# GD32F207RG.net
KiCad netlist of a schematic drawn in EAGLE
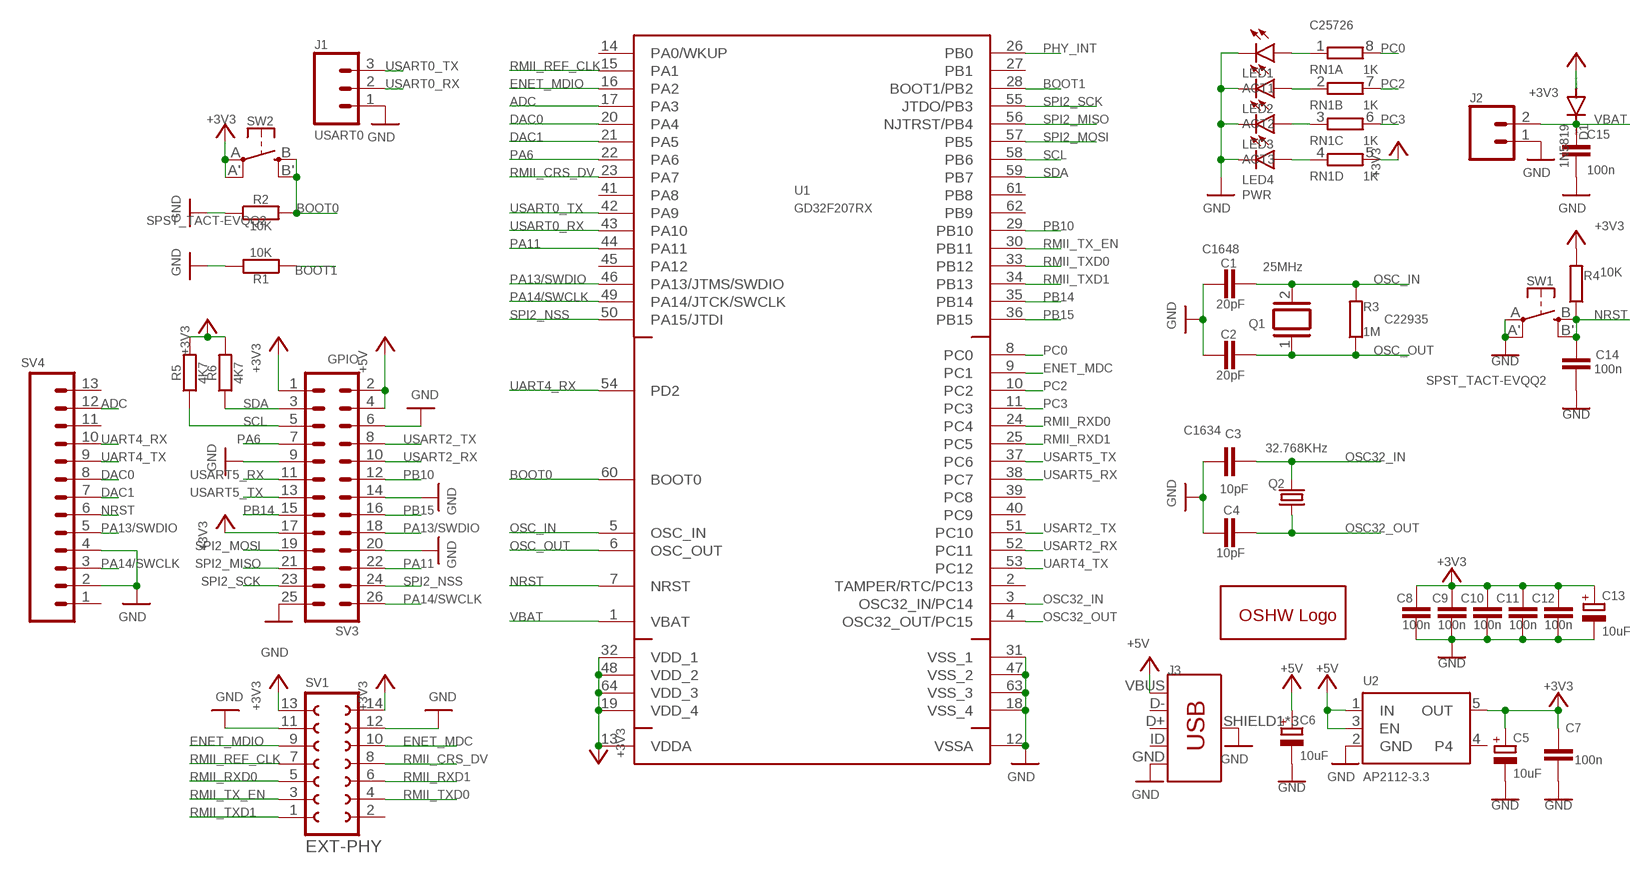
[diagram p0: schematic, sheet 1]

(export (version "E")
  (design (tool "Eeschema 10.0.6"))
  (components
    (comp (ref "C1")
      (value "20pF")
      (footprint "eagle-import:C0603")
      (fields (field (name "JLCPCB") "C1648"))
      (libsource (lib "eagle-import") (part "C-EUC0603"))
    )
    (comp (ref "C2")
      (value "20pF")
      (footprint "eagle-import:C0603")
      (libsource (lib "eagle-import") (part "C-EUC0603"))
    )
    (comp (ref "C3")
      (value "10pF")
      (footprint "eagle-import:C0603")
      (fields (field (name "JLCPCB") "C1634"))
      (libsource (lib "eagle-import") (part "C-EUC0603"))
    )
    (comp (ref "C4")
      (value "10pF")
      (footprint "eagle-import:C0603")
      (libsource (lib "eagle-import") (part "C-EUC0603"))
    )
    (comp (ref "C5")
      (value "10uF")
      (footprint "eagle-import:A_3216-18R")
      (libsource (lib "eagle-import") (part "CPOL-EUA/3216-18R"))
    )
    (comp (ref "C6")
      (value "10uF")
      (footprint "eagle-import:A_3216-18R")
      (libsource (lib "eagle-import") (part "CPOL-EUA/3216-18R"))
    )
    (comp (ref "C7")
      (value "100n")
      (footprint "eagle-import:C0603")
      (libsource (lib "eagle-import") (part "C-EUC0603"))
    )
    (comp (ref "C8")
      (value "100n")
      (footprint "eagle-import:C0603")
      (libsource (lib "eagle-import") (part "C-EUC0603"))
    )
    (comp (ref "C9")
      (value "100n")
      (footprint "eagle-import:C0603")
      (libsource (lib "eagle-import") (part "C-EUC0603"))
    )
    (comp (ref "C10")
      (value "100n")
      (footprint "eagle-import:C0603")
      (libsource (lib "eagle-import") (part "C-EUC0603"))
    )
    (comp (ref "C11")
      (value "100n")
      (footprint "eagle-import:C0603")
      (libsource (lib "eagle-import") (part "C-EUC0603"))
    )
    (comp (ref "C12")
      (value "100n")
      (footprint "eagle-import:C0603")
      (libsource (lib "eagle-import") (part "C-EUC0603"))
    )
    (comp (ref "C13")
      (value "10uF")
      (footprint "eagle-import:A_3216-18R")
      (libsource (lib "eagle-import") (part "CPOL-EUA/3216-18R"))
    )
    (comp (ref "C14")
      (value "100n")
      (footprint "eagle-import:C0603")
      (libsource (lib "eagle-import") (part "C-EUC0603"))
    )
    (comp (ref "C15")
      (value "100n")
      (footprint "eagle-import:C0603")
      (libsource (lib "eagle-import") (part "C-EUC0603"))
    )
    (comp (ref "D1")
      (value "1N5819")
      (footprint "eagle-import:SOD323-R")
      (libsource (lib "eagle-import") (part "DIODE-SOD323-R"))
    )
    (comp (ref "GOLD_ORB_SM1")
      (value "OSHWLOGOLOGO5MM")
      (footprint "eagle-import:OSHW_5MM")
      (libsource (lib "eagle-import") (part "OSHWLOGOLOGO5MM"))
    )
    (comp (ref "J1")
      (value "USART0")
      (footprint "eagle-import:1X03")
      (libsource (lib "eagle-import") (part "CONN_03"))
    )
    (comp (ref "J2")
      (value "CONN_02JST-PTH-2")
      (footprint "eagle-import:JST-2-PTH")
      (libsource (lib "eagle-import") (part "CONN_02JST-PTH-2"))
    )
    (comp (ref "J3")
      (value "USB_MICRO-B_FEMALE-SMT")
      (footprint "eagle-import:USB-B-MICRO-SMD")
      (libsource (lib "eagle-import") (part "USB_MICRO-B_FEMALE-SMT"))
    )
    (comp (ref "LED1")
      (value "ACT1")
      (footprint "eagle-import:CHIP-LED0603")
      (libsource (lib "eagle-import") (part "LEDCHIP-LED0603"))
    )
    (comp (ref "LED2")
      (value "ACT2")
      (footprint "eagle-import:CHIP-LED0603")
      (libsource (lib "eagle-import") (part "LEDCHIP-LED0603"))
    )
    (comp (ref "LED3")
      (value "ACT3")
      (footprint "eagle-import:CHIP-LED0603")
      (libsource (lib "eagle-import") (part "LEDCHIP-LED0603"))
    )
    (comp (ref "LED4")
      (value "PWR")
      (footprint "eagle-import:CHIP-LED0603")
      (libsource (lib "eagle-import") (part "LEDCHIP-LED0603"))
    )
    (comp (ref "Q1")
      (value "25MHz")
      (footprint "eagle-import:QS")
      (libsource (lib "eagle-import") (part "XTAL/S"))
    )
    (comp (ref "Q2")
      (value "32.768KHz")
      (footprint "eagle-import:TC26H")
      (libsource (lib "eagle-import") (part "CRYSTALTC26H"))
    )
    (comp (ref "R1")
      (value "10K")
      (footprint "eagle-import:R0603")
      (libsource (lib "eagle-import") (part "R-EU_R0603"))
    )
    (comp (ref "R2")
      (value "10K")
      (footprint "eagle-import:R0603")
      (libsource (lib "eagle-import") (part "R-EU_R0603"))
    )
    (comp (ref "R3")
      (value "1M")
      (footprint "eagle-import:R0603")
      (fields (field (name "JLCPCB") "C22935"))
      (libsource (lib "eagle-import") (part "R-EU_R0603"))
    )
    (comp (ref "R4")
      (value "10K")
      (footprint "eagle-import:R0603")
      (libsource (lib "eagle-import") (part "R-EU_R0603"))
    )
    (comp (ref "R5")
      (value "4K7")
      (footprint "eagle-import:R0603")
      (libsource (lib "eagle-import") (part "R-EU_R0603"))
    )
    (comp (ref "R6")
      (value "4K7")
      (footprint "eagle-import:R0603")
      (libsource (lib "eagle-import") (part "R-EU_R0603"))
    )
    (comp (ref "RN1")
      (value "1K")
      (footprint "eagle-import:4X0402ARV341")
      (fields (field (name "JLCPCB") "C25726"))
      (libsource (lib "eagle-import") (part "4R-N0402ARV341"))
    )
    (comp (ref "SV1")
      (value "EXT-PHY")
      (footprint "eagle-import:FE07-2W")
      (libsource (lib "eagle-import") (part "FE07-2W"))
    )
    (comp (ref "SV3")
      (value "GPIO")
      (footprint "eagle-import:MA13-2")
      (libsource (lib "eagle-import") (part "MA13-2"))
    )
    (comp (ref "SV4")
      (value "CONN_13")
      (footprint "eagle-import:1X13")
      (libsource (lib "eagle-import") (part "CONN_13"))
    )
    (comp (ref "SW1")
      (value "SPST_TACT-EVQQ2")
      (footprint "eagle-import:EVQ-Q2")
      (libsource (lib "eagle-import") (part "SPST_TACT-EVQQ2"))
    )
    (comp (ref "SW2")
      (value "SPST_TACT-EVQQ2")
      (footprint "eagle-import:EVQ-Q2")
      (libsource (lib "eagle-import") (part "SPST_TACT-EVQQ2"))
    )
    (comp (ref "U1")
      (value "GD32F207RX")
      (footprint "eagle-import:LQFP64")
      (libsource (lib "eagle-import") (part "GD32F207RX"))
    )
    (comp (ref "U2")
      (value "AP2112-3.3")
      (footprint "eagle-import:SOT23-5")
      (libsource (lib "eagle-import") (part "VREG_SOT23-5"))
    )
  )
  (nets
    (net (code "1") (name "+3V3") (class "Default")
      (node (ref "C10") (pin "1") (pinfunction "1_1") (pintype "passive"))
      (node (ref "C11") (pin "1") (pinfunction "1_1") (pintype "passive"))
      (node (ref "C12") (pin "1") (pinfunction "1_1") (pintype "passive"))
      (node (ref "C13") (pin "+") (pinfunction "+_+") (pintype "passive"))
      (node (ref "C5") (pin "+") (pinfunction "+_+") (pintype "passive"))
      (node (ref "C7") (pin "1") (pinfunction "1_1") (pintype "passive"))
      (node (ref "C8") (pin "1") (pinfunction "1_1") (pintype "passive"))
      (node (ref "C9") (pin "1") (pinfunction "1_1") (pintype "passive"))
      (node (ref "D1") (pin "A") (pinfunction "A_A") (pintype "passive"))
      (node (ref "R4") (pin "2") (pinfunction "2_2") (pintype "passive"))
      (node (ref "R5") (pin "2") (pinfunction "2_2") (pintype "passive"))
      (node (ref "R6") (pin "2") (pinfunction "2_2") (pintype "passive"))
      (node (ref "RN1") (pin "5") (pinfunction "2_5") (pintype "passive"))
      (node (ref "SV1") (pin "13") (pinfunction "13_13") (pintype "passive"))
      (node (ref "SV1") (pin "14") (pinfunction "14_14") (pintype "passive"))
      (node (ref "SV3") (pin "1") (pinfunction "1_1") (pintype "passive"))
      (node (ref "SV3") (pin "17") (pinfunction "17_17") (pintype "passive"))
      (node (ref "SW2") (pin "A") (pinfunction "P_A") (pintype "passive"))
      (node (ref "SW2") (pin "A'") (pinfunction "P1_A'") (pintype "passive"))
      (node (ref "U1") (pin "13") (pinfunction "VDDA_13") (pintype "power_in"))
      (node (ref "U1") (pin "19") (pinfunction "VDD_4_19") (pintype "power_in"))
      (node (ref "U1") (pin "32") (pinfunction "VDD_1_32") (pintype "power_in"))
      (node (ref "U1") (pin "48") (pinfunction "VDD_2_48") (pintype "power_in"))
      (node (ref "U1") (pin "64") (pinfunction "VDD_3_64") (pintype "power_in"))
      (node (ref "U2") (pin "5") (pinfunction "OUT_5") (pintype "power_in"))
    )
    (net (code "2") (name "+5V") (class "Default")
      (node (ref "C6") (pin "+") (pinfunction "+_+") (pintype "passive"))
      (node (ref "J3") (pin "VBUS") (pinfunction "VBUS_VBUS") (pintype "power_in"))
      (node (ref "SV3") (pin "2") (pinfunction "2_2") (pintype "passive"))
      (node (ref "SV3") (pin "4") (pinfunction "4_4") (pintype "passive"))
      (node (ref "U2") (pin "1") (pinfunction "IN_1") (pintype "power_in"))
      (node (ref "U2") (pin "3") (pinfunction "EN_3") (pintype "input"))
    )
    (net (code "3") (name "/ADC") (class "Default")
      (node (ref "SV4") (pin "12") (pinfunction "12_12") (pintype "passive"))
      (node (ref "U1") (pin "17") (pinfunction "PA3_17") (pintype "bidirectional"))
    )
    (net (code "4") (name "/BOOT0") (class "Default")
      (node (ref "R2") (pin "2") (pinfunction "2_2") (pintype "passive"))
      (node (ref "SW2") (pin "B") (pinfunction "S_B") (pintype "passive"))
      (node (ref "SW2") (pin "B'") (pinfunction "S1_B'") (pintype "passive"))
      (node (ref "U1") (pin "60") (pinfunction "BOOT0_60") (pintype "bidirectional"))
    )
    (net (code "5") (name "/BOOT1") (class "Default")
      (node (ref "R1") (pin "1") (pinfunction "1_1") (pintype "passive"))
      (node (ref "U1") (pin "28") (pinfunction "BOOT1/PB2_28") (pintype "bidirectional"))
    )
    (net (code "6") (name "/DAC0") (class "Default")
      (node (ref "SV4") (pin "8") (pinfunction "8_8") (pintype "passive"))
      (node (ref "U1") (pin "20") (pinfunction "PA4_20") (pintype "bidirectional"))
    )
    (net (code "7") (name "/DAC1") (class "Default")
      (node (ref "SV4") (pin "7") (pinfunction "7_7") (pintype "passive"))
      (node (ref "U1") (pin "21") (pinfunction "PA5_21") (pintype "bidirectional"))
    )
    (net (code "8") (name "/ENET_MDC") (class "Default")
      (node (ref "SV1") (pin "10") (pinfunction "10_10") (pintype "passive"))
      (node (ref "U1") (pin "9") (pinfunction "PC1_9") (pintype "bidirectional"))
    )
    (net (code "9") (name "/ENET_MDIO") (class "Default")
      (node (ref "SV1") (pin "9") (pinfunction "9_9") (pintype "passive"))
      (node (ref "U1") (pin "16") (pinfunction "PA2_16") (pintype "bidirectional"))
    )
    (net (code "10") (name "/NRST") (class "Default")
      (node (ref "C14") (pin "1") (pinfunction "1_1") (pintype "passive"))
      (node (ref "R4") (pin "1") (pinfunction "1_1") (pintype "passive"))
      (node (ref "SV4") (pin "6") (pinfunction "6_6") (pintype "passive"))
      (node (ref "SW1") (pin "B") (pinfunction "S_B") (pintype "passive"))
      (node (ref "SW1") (pin "B'") (pinfunction "S1_B'") (pintype "passive"))
      (node (ref "U1") (pin "7") (pinfunction "NRST_7") (pintype "power_in"))
    )
    (net (code "11") (name "/OSC32_IN") (class "Default")
      (node (ref "C3") (pin "2") (pinfunction "2_2") (pintype "passive"))
      (node (ref "Q2") (pin "2") (pinfunction "2_2") (pintype "passive"))
      (node (ref "U1") (pin "3") (pinfunction "OSC32_IN/PC14_3") (pintype "bidirectional"))
    )
    (net (code "12") (name "/OSC32_OUT") (class "Default")
      (node (ref "C4") (pin "2") (pinfunction "2_2") (pintype "passive"))
      (node (ref "Q2") (pin "1") (pinfunction "1_1") (pintype "passive"))
      (node (ref "U1") (pin "4") (pinfunction "OSC32_OUT/PC15_4") (pintype "bidirectional"))
    )
    (net (code "13") (name "/OSC_IN") (class "Default")
      (node (ref "C1") (pin "2") (pinfunction "2_2") (pintype "passive"))
      (node (ref "Q1") (pin "2") (pinfunction "2_2") (pintype "passive"))
      (node (ref "R3") (pin "2") (pinfunction "2_2") (pintype "passive"))
      (node (ref "U1") (pin "5") (pinfunction "OSC_IN_5") (pintype "bidirectional"))
    )
    (net (code "14") (name "/OSC_OUT") (class "Default")
      (node (ref "C2") (pin "2") (pinfunction "2_2") (pintype "passive"))
      (node (ref "Q1") (pin "1") (pinfunction "1_1") (pintype "passive"))
      (node (ref "R3") (pin "1") (pinfunction "1_1") (pintype "passive"))
      (node (ref "U1") (pin "6") (pinfunction "OSC_OUT_6") (pintype "bidirectional"))
    )
    (net (code "15") (name "/PA6") (class "Default")
      (node (ref "SV3") (pin "7") (pinfunction "7_7") (pintype "passive"))
      (node (ref "U1") (pin "22") (pinfunction "PA6_22") (pintype "bidirectional"))
    )
    (net (code "16") (name "/PA11") (class "Default")
      (node (ref "SV3") (pin "22") (pinfunction "22_22") (pintype "passive"))
      (node (ref "U1") (pin "44") (pinfunction "PA11_44") (pintype "bidirectional"))
    )
    (net (code "17") (name "/PA13{slash}SWDIO") (class "Default")
      (node (ref "SV3") (pin "18") (pinfunction "18_18") (pintype "passive"))
      (node (ref "SV4") (pin "5") (pinfunction "5_5") (pintype "passive"))
      (node (ref "U1") (pin "46") (pinfunction "PA13/JTMS/SWDIO_46") (pintype "bidirectional"))
    )
    (net (code "18") (name "/PA14{slash}SWCLK") (class "Default")
      (node (ref "SV3") (pin "26") (pinfunction "26_26") (pintype "passive"))
      (node (ref "SV4") (pin "3") (pinfunction "3_3") (pintype "passive"))
      (node (ref "U1") (pin "49") (pinfunction "PA14/JTCK/SWCLK_49") (pintype "bidirectional"))
    )
    (net (code "19") (name "/PB10") (class "Default")
      (node (ref "SV3") (pin "12") (pinfunction "12_12") (pintype "passive"))
      (node (ref "U1") (pin "29") (pinfunction "PB10_29") (pintype "bidirectional"))
    )
    (net (code "20") (name "/PB14") (class "Default")
      (node (ref "SV3") (pin "15") (pinfunction "15_15") (pintype "passive"))
      (node (ref "U1") (pin "35") (pinfunction "PB14_35") (pintype "bidirectional"))
    )
    (net (code "21") (name "/PB15") (class "Default")
      (node (ref "SV3") (pin "16") (pinfunction "16_16") (pintype "passive"))
      (node (ref "U1") (pin "36") (pinfunction "PB15_36") (pintype "bidirectional"))
    )
    (net (code "22") (name "/PC0") (class "Default")
      (node (ref "RN1") (pin "8") (pinfunction "2_8") (pintype "passive"))
      (node (ref "U1") (pin "8") (pinfunction "PC0_8") (pintype "bidirectional"))
    )
    (net (code "23") (name "/PC2") (class "Default")
      (node (ref "RN1") (pin "7") (pinfunction "2_7") (pintype "passive"))
      (node (ref "U1") (pin "10") (pinfunction "PC2_10") (pintype "bidirectional"))
    )
    (net (code "24") (name "/PC3") (class "Default")
      (node (ref "RN1") (pin "6") (pinfunction "2_6") (pintype "passive"))
      (node (ref "U1") (pin "11") (pinfunction "PC3_11") (pintype "bidirectional"))
    )
    (net (code "25") (name "/PHY_INT") (class "Default")
      (node (ref "U1") (pin "26") (pinfunction "PB0_26") (pintype "bidirectional"))
    )
    (net (code "26") (name "/RMII_CRS_DV") (class "Default")
      (node (ref "SV1") (pin "8") (pinfunction "8_8") (pintype "passive"))
      (node (ref "U1") (pin "23") (pinfunction "PA7_23") (pintype "bidirectional"))
    )
    (net (code "27") (name "/RMII_REF_CLK") (class "Default")
      (node (ref "SV1") (pin "7") (pinfunction "7_7") (pintype "passive"))
      (node (ref "U1") (pin "15") (pinfunction "PA1_15") (pintype "bidirectional"))
    )
    (net (code "28") (name "/RMII_RXD0") (class "Default")
      (node (ref "SV1") (pin "5") (pinfunction "5_5") (pintype "passive"))
      (node (ref "U1") (pin "24") (pinfunction "PC4_24") (pintype "bidirectional"))
    )
    (net (code "29") (name "/RMII_RXD1") (class "Default")
      (node (ref "SV1") (pin "6") (pinfunction "6_6") (pintype "passive"))
      (node (ref "U1") (pin "25") (pinfunction "PC5_25") (pintype "bidirectional"))
    )
    (net (code "30") (name "/RMII_TXD0") (class "Default")
      (node (ref "SV1") (pin "4") (pinfunction "4_4") (pintype "passive"))
      (node (ref "U1") (pin "33") (pinfunction "PB12_33") (pintype "bidirectional"))
    )
    (net (code "31") (name "/RMII_TXD1") (class "Default")
      (node (ref "SV1") (pin "1") (pinfunction "1_1") (pintype "passive"))
      (node (ref "U1") (pin "34") (pinfunction "PB13_34") (pintype "bidirectional"))
    )
    (net (code "32") (name "/RMII_TX_EN") (class "Default")
      (node (ref "SV1") (pin "3") (pinfunction "3_3") (pintype "passive"))
      (node (ref "U1") (pin "30") (pinfunction "PB11_30") (pintype "bidirectional"))
    )
    (net (code "33") (name "/SCL") (class "Default")
      (node (ref "R5") (pin "1") (pinfunction "1_1") (pintype "passive"))
      (node (ref "SV3") (pin "5") (pinfunction "5_5") (pintype "passive"))
      (node (ref "U1") (pin "58") (pinfunction "PB6_58") (pintype "bidirectional"))
    )
    (net (code "34") (name "/SDA") (class "Default")
      (node (ref "R6") (pin "1") (pinfunction "1_1") (pintype "passive"))
      (node (ref "SV3") (pin "3") (pinfunction "3_3") (pintype "passive"))
      (node (ref "U1") (pin "59") (pinfunction "PB7_59") (pintype "bidirectional"))
    )
    (net (code "35") (name "/SPI2_MISO") (class "Default")
      (node (ref "SV3") (pin "21") (pinfunction "21_21") (pintype "passive"))
      (node (ref "U1") (pin "56") (pinfunction "NJTRST/PB4_56") (pintype "bidirectional"))
    )
    (net (code "36") (name "/SPI2_MOSI") (class "Default")
      (node (ref "SV3") (pin "19") (pinfunction "19_19") (pintype "passive"))
      (node (ref "U1") (pin "57") (pinfunction "PB5_57") (pintype "bidirectional"))
    )
    (net (code "37") (name "/SPI2_NSS") (class "Default")
      (node (ref "SV3") (pin "24") (pinfunction "24_24") (pintype "passive"))
      (node (ref "U1") (pin "50") (pinfunction "PA15/JTDI_50") (pintype "bidirectional"))
    )
    (net (code "38") (name "/SPI2_SCK") (class "Default")
      (node (ref "SV3") (pin "23") (pinfunction "23_23") (pintype "passive"))
      (node (ref "U1") (pin "55") (pinfunction "JTDO/PB3_55") (pintype "bidirectional"))
    )
    (net (code "39") (name "/UART4_RX") (class "Default")
      (node (ref "SV4") (pin "10") (pinfunction "10_10") (pintype "passive"))
      (node (ref "U1") (pin "54") (pinfunction "PD2_54") (pintype "bidirectional"))
    )
    (net (code "40") (name "/UART4_TX") (class "Default")
      (node (ref "SV4") (pin "9") (pinfunction "9_9") (pintype "passive"))
      (node (ref "U1") (pin "53") (pinfunction "PC12_53") (pintype "bidirectional"))
    )
    (net (code "41") (name "/USART0_RX") (class "Default")
      (node (ref "J1") (pin "2") (pinfunction "2_2") (pintype "passive"))
      (node (ref "U1") (pin "43") (pinfunction "PA10_43") (pintype "bidirectional"))
    )
    (net (code "42") (name "/USART0_TX") (class "Default")
      (node (ref "J1") (pin "3") (pinfunction "3_3") (pintype "passive"))
      (node (ref "U1") (pin "42") (pinfunction "PA9_42") (pintype "bidirectional"))
    )
    (net (code "43") (name "/USART2_RX") (class "Default")
      (node (ref "SV3") (pin "10") (pinfunction "10_10") (pintype "passive"))
      (node (ref "U1") (pin "52") (pinfunction "PC11_52") (pintype "bidirectional"))
    )
    (net (code "44") (name "/USART2_TX") (class "Default")
      (node (ref "SV3") (pin "8") (pinfunction "8_8") (pintype "passive"))
      (node (ref "U1") (pin "51") (pinfunction "PC10_51") (pintype "bidirectional"))
    )
    (net (code "45") (name "/USART5_RX") (class "Default")
      (node (ref "SV3") (pin "11") (pinfunction "11_11") (pintype "passive"))
      (node (ref "U1") (pin "38") (pinfunction "PC7_38") (pintype "bidirectional"))
    )
    (net (code "46") (name "/USART5_TX") (class "Default")
      (node (ref "SV3") (pin "13") (pinfunction "13_13") (pintype "passive"))
      (node (ref "U1") (pin "37") (pinfunction "PC6_37") (pintype "bidirectional"))
    )
    (net (code "47") (name "/VBAT") (class "Default")
      (node (ref "C15") (pin "1") (pinfunction "1_1") (pintype "passive"))
      (node (ref "D1") (pin "C") (pinfunction "C_C") (pintype "passive"))
      (node (ref "J2") (pin "2") (pinfunction "2_2") (pintype "passive"))
      (node (ref "U1") (pin "1") (pinfunction "VBAT_1") (pintype "power_in"))
    )
    (net (code "48") (name "GND") (class "Default")
      (node (ref "C1") (pin "1") (pinfunction "1_1") (pintype "passive"))
      (node (ref "C10") (pin "2") (pinfunction "2_2") (pintype "passive"))
      (node (ref "C11") (pin "2") (pinfunction "2_2") (pintype "passive"))
      (node (ref "C12") (pin "2") (pinfunction "2_2") (pintype "passive"))
      (node (ref "C13") (pin "-") (pinfunction "-_-") (pintype "passive"))
      (node (ref "C14") (pin "2") (pinfunction "2_2") (pintype "passive"))
      (node (ref "C15") (pin "2") (pinfunction "2_2") (pintype "passive"))
      (node (ref "C2") (pin "1") (pinfunction "1_1") (pintype "passive"))
      (node (ref "C3") (pin "1") (pinfunction "1_1") (pintype "passive"))
      (node (ref "C4") (pin "1") (pinfunction "1_1") (pintype "passive"))
      (node (ref "C5") (pin "-") (pinfunction "-_-") (pintype "passive"))
      (node (ref "C6") (pin "-") (pinfunction "-_-") (pintype "passive"))
      (node (ref "C7") (pin "2") (pinfunction "2_2") (pintype "passive"))
      (node (ref "C8") (pin "2") (pinfunction "2_2") (pintype "passive"))
      (node (ref "C9") (pin "2") (pinfunction "2_2") (pintype "passive"))
      (node (ref "J1") (pin "1") (pinfunction "1_1") (pintype "passive"))
      (node (ref "J2") (pin "1") (pinfunction "1_1") (pintype "passive"))
      (node (ref "J3") (pin "GND") (pinfunction "GND_GND") (pintype "power_in"))
      (node (ref "J3") (pin "SHIELD1") (pinfunction "SHIELD_SHIELD1") (pintype "bidirectional"))
      (node (ref "J3") (pin "SHIELD2") (pinfunction "SHIELD_SHIELD2") (pintype "bidirectional"))
      (node (ref "J3") (pin "SHIELD3") (pinfunction "SHIELD_SHIELD3") (pintype "bidirectional"))
      (node (ref "LED1") (pin "C") (pinfunction "C_C") (pintype "passive"))
      (node (ref "LED2") (pin "C") (pinfunction "C_C") (pintype "passive"))
      (node (ref "LED3") (pin "C") (pinfunction "C_C") (pintype "passive"))
      (node (ref "LED4") (pin "C") (pinfunction "C_C") (pintype "passive"))
      (node (ref "R1") (pin "2") (pinfunction "2_2") (pintype "passive"))
      (node (ref "R2") (pin "1") (pinfunction "1_1") (pintype "passive"))
      (node (ref "SV1") (pin "11") (pinfunction "11_11") (pintype "passive"))
      (node (ref "SV1") (pin "12") (pinfunction "12_12") (pintype "passive"))
      (node (ref "SV3") (pin "14") (pinfunction "14_14") (pintype "passive"))
      (node (ref "SV3") (pin "20") (pinfunction "20_20") (pintype "passive"))
      (node (ref "SV3") (pin "25") (pinfunction "25_25") (pintype "passive"))
      (node (ref "SV3") (pin "6") (pinfunction "6_6") (pintype "passive"))
      (node (ref "SV3") (pin "9") (pinfunction "9_9") (pintype "passive"))
      (node (ref "SV4") (pin "2") (pinfunction "2_2") (pintype "passive"))
      (node (ref "SV4") (pin "4") (pinfunction "4_4") (pintype "passive"))
      (node (ref "SW1") (pin "A") (pinfunction "P_A") (pintype "passive"))
      (node (ref "SW1") (pin "A'") (pinfunction "P1_A'") (pintype "passive"))
      (node (ref "U1") (pin "12") (pinfunction "VSSA_12") (pintype "power_in"))
      (node (ref "U1") (pin "18") (pinfunction "VSS_4_18") (pintype "power_in"))
      (node (ref "U1") (pin "31") (pinfunction "VSS_1_31") (pintype "power_in"))
      (node (ref "U1") (pin "47") (pinfunction "VSS_2_47") (pintype "power_in"))
      (node (ref "U1") (pin "63") (pinfunction "VSS_3_63") (pintype "power_in"))
      (node (ref "U2") (pin "2") (pinfunction "GND_2") (pintype "power_in"))
    )
    (net (code "49") (name "Net-(LED1-PadA)") (class "Default")
      (node (ref "LED1") (pin "A") (pinfunction "A_A") (pintype "passive"))
      (node (ref "RN1") (pin "1") (pinfunction "1_1") (pintype "passive"))
    )
    (net (code "50") (name "Net-(RN1B-1)") (class "Default")
      (node (ref "LED2") (pin "A") (pinfunction "A_A") (pintype "passive"))
      (node (ref "RN1") (pin "2") (pinfunction "1_2") (pintype "passive"))
    )
    (net (code "51") (name "Net-(RN1C-1)") (class "Default")
      (node (ref "LED3") (pin "A") (pinfunction "A_A") (pintype "passive"))
      (node (ref "RN1") (pin "3") (pinfunction "1_3") (pintype "passive"))
    )
    (net (code "52") (name "Net-(RN1D-1)") (class "Default")
      (node (ref "LED4") (pin "A") (pinfunction "A_A") (pintype "passive"))
      (node (ref "RN1") (pin "4") (pinfunction "1_4") (pintype "passive"))
    )
    (net (code "53") (name "unconnected-(J3-PadD+)") (class "Default")
      (node (ref "J3") (pin "D+") (pinfunction "D+_D+") (pintype "bidirectional"))
    )
    (net (code "54") (name "unconnected-(J3-PadD-)") (class "Default")
      (node (ref "J3") (pin "D-") (pinfunction "D-_D-") (pintype "bidirectional"))
    )
    (net (code "55") (name "unconnected-(J3-PadID)") (class "Default")
      (node (ref "J3") (pin "ID") (pinfunction "ID_ID") (pintype "bidirectional"))
    )
    (net (code "56") (name "unconnected-(SV1-Pad2)") (class "Default")
      (node (ref "SV1") (pin "2") (pinfunction "2_2") (pintype "passive"))
    )
    (net (code "57") (name "unconnected-(SV4-Pad1)") (class "Default")
      (node (ref "SV4") (pin "1") (pinfunction "1_1") (pintype "passive"))
    )
    (net (code "58") (name "unconnected-(SV4-Pad11)") (class "Default")
      (node (ref "SV4") (pin "11") (pinfunction "11_11") (pintype "passive"))
    )
    (net (code "59") (name "unconnected-(SV4-Pad13)") (class "Default")
      (node (ref "SV4") (pin "13") (pinfunction "13_13") (pintype "passive"))
    )
    (net (code "60") (name "unconnected-(U1-PA0{slash}WKUP-Pad14)") (class "Default")
      (node (ref "U1") (pin "14") (pinfunction "PA0/WKUP_14") (pintype "bidirectional"))
    )
    (net (code "61") (name "unconnected-(U1-PA8-Pad41)") (class "Default")
      (node (ref "U1") (pin "41") (pinfunction "PA8_41") (pintype "bidirectional"))
    )
    (net (code "62") (name "unconnected-(U1-PA12-Pad45)") (class "Default")
      (node (ref "U1") (pin "45") (pinfunction "PA12_45") (pintype "bidirectional"))
    )
    (net (code "63") (name "unconnected-(U1-PB1-Pad27)") (class "Default")
      (node (ref "U1") (pin "27") (pinfunction "PB1_27") (pintype "bidirectional"))
    )
    (net (code "64") (name "unconnected-(U1-PB8-Pad61)") (class "Default")
      (node (ref "U1") (pin "61") (pinfunction "PB8_61") (pintype "bidirectional"))
    )
    (net (code "65") (name "unconnected-(U1-PB9-Pad62)") (class "Default")
      (node (ref "U1") (pin "62") (pinfunction "PB9_62") (pintype "bidirectional"))
    )
    (net (code "66") (name "unconnected-(U1-PC8-Pad39)") (class "Default")
      (node (ref "U1") (pin "39") (pinfunction "PC8_39") (pintype "bidirectional"))
    )
    (net (code "67") (name "unconnected-(U1-PC9-Pad40)") (class "Default")
      (node (ref "U1") (pin "40") (pinfunction "PC9_40") (pintype "bidirectional"))
    )
    (net (code "68") (name "unconnected-(U1-TAMPER{slash}RTC{slash}PC13-Pad2)") (class "Default")
      (node (ref "U1") (pin "2") (pinfunction "TAMPER/RTC/PC13_2") (pintype "bidirectional"))
    )
    (net (code "69") (name "unconnected-(U2-P4-Pad4)") (class "Default")
      (node (ref "U2") (pin "4") (pinfunction "P4_4") (pintype "bidirectional"))
    )
  )
)
